# 3.net
KiCad netlist of a schematic drawn in Altium Designer
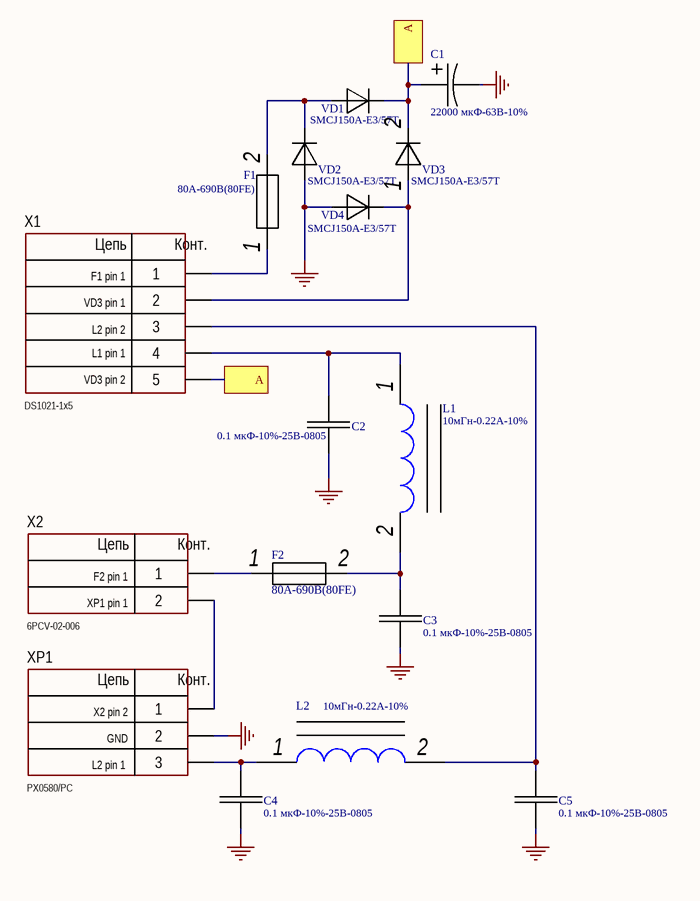
[diagram p0: Э3.SchDoc]

(export (version "E")
  (design (tool "Eeschema 10.0.6"))
  (components
    (comp (ref "C1")
      (value "22000 мкФ-63В-10%")
      (footprint "condpolar")
      (fields (field (name "MANUFACTURER") "Тайвань") (field (name "PARTNUMBER") "ECAP22000uF/63V,85°C"))
      (libsource (lib "resistor") (part "конденсатор_поляр"))
    )
    (comp (ref "C2")
      (value "0.1 мкФ-10%-25В-0805")
      (footprint "Condensator")
      (fields
        (field (name "MANUFACTURER") "Murata Electronics")
        (field (name "PARTNUMBER") "GRM21BR71E104KA01L")
      )
      (libsource (lib "resistor") (part "конденсатор"))
    )
    (comp (ref "C3")
      (value "0.1 мкФ-10%-25В-0805")
      (footprint "Condensator")
      (fields
        (field (name "MANUFACTURER") "Murata Electronics")
        (field (name "PARTNUMBER") "GRM21BR71E104KA01L")
      )
      (libsource (lib "resistor") (part "конденсатор"))
    )
    (comp (ref "C4")
      (value "0.1 мкФ-10%-25В-0805")
      (footprint "Condensator")
      (fields
        (field (name "MANUFACTURER") "Murata Electronics")
        (field (name "PARTNUMBER") "GRM21BR71E104KA01L")
      )
      (libsource (lib "resistor") (part "конденсатор"))
    )
    (comp (ref "C5")
      (value "0.1 мкФ-10%-25В-0805")
      (footprint "Condensator")
      (fields
        (field (name "MANUFACTURER") "Murata Electronics")
        (field (name "PARTNUMBER") "GRM21BR71E104KA01L")
      )
      (libsource (lib "resistor") (part "конденсатор"))
    )
    (comp (ref "F1")
      (value "80А-690В(80FE)")
      (footprint "FUSE 80")
      (fields (field (name "MANUFACTURER") "Eaton") (field (name "PARTNUMBER") "80FE"))
      (libsource (lib "resistor") (part "FUSE"))
    )
    (comp (ref "F2")
      (value "80А-690В(80FE)")
      (footprint "FUSE 80")
      (fields (field (name "MANUFACTURER") "Eaton") (field (name "PARTNUMBER") "80FE"))
      (libsource (lib "") (part "FUSE_1"))
    )
    (comp (ref "L1")
      (value "10мГн-0.22A-10%")
      (footprint "inductor")
      (fields (field (name "MANUFACTURER") "Kemet Electronics") (field (name "PARTNUMBER") "SBC6-103-161"))
      (libsource (lib "resistor") (part "inductor"))
    )
    (comp (ref "L2")
      (value "10мГн-0.22A-10%")
      (footprint "inductor")
      (fields (field (name "MANUFACTURER") "Kemet Electronics"))
      (libsource (lib "resistor") (part "inductor"))
    )
    (comp (ref "VD1")
      (value "SMCJ150A-E3/57T")
      (footprint "DIOD")
      (fields (field (name "MANUFACTURER") "VISHAY INTERTECHNOLOGY INC."))
      (libsource (lib "resistor") (part "Diod"))
    )
    (comp (ref "VD2")
      (value "SMCJ150A-E3/57T")
      (footprint "DIOD")
      (fields (field (name "MANUFACTURER") "VISHAY INTERTECHNOLOGY INC."))
      (libsource (lib "resistor") (part "Diod"))
    )
    (comp (ref "VD3")
      (value "SMCJ150A-E3/57T")
      (footprint "DIOD")
      (fields (field (name "MANUFACTURER") "VISHAY INTERTECHNOLOGY INC."))
      (libsource (lib "") (part "Diod_1"))
    )
    (comp (ref "VD4")
      (value "SMCJ150A-E3/57T")
      (footprint "DIOD")
      (fields (field (name "MANUFACTURER") "VISHAY INTERTECHNOLOGY INC."))
      (libsource (lib "resistor") (part "Diod"))
    )
    (comp (ref "X1")
      (value "~")
      (footprint "CON: PLS-5")
      (fields
        (field (name "MANUFACTURER") "Connfly")
        (field (name "VALUEMANUFACTURERPARTNUMBER") "Connector, 5pin, 2.54mm, 500VAC, 3A")
        (field (name "PARTNUMBER") "PLS-5")
        (field (name "COMMENTTEXT") "DS1021-1x5")
      )
      (libsource (lib "connector") (part "PLS-5"))
    )
    (comp (ref "X2")
      (value "~")
      (footprint "CON: 6PCV-02-006")
      (fields
        (field (name "MANUFACTURER") "TE Connectivity")
        (field (name "VALUEMANUFACTURERPARTNUMBER") "Connector, 2pin, 9.53mm, 300VAC, 25A")
        (field (name "PARTNUMBER") "6PCV-02-006")
        (field (name "COMMENTTEXT") "6PCV-02-006")
      )
      (libsource (lib "connector") (part "Connector_6PCV-02"))
    )
    (comp (ref "XP1")
      (value "~")
      (footprint "AC")
      (fields
        (field (name "MANUFACTURER") "Connfly")
        (field (name "VALUEMANUFACTURERPARTNUMBER") "Connector, 3pin, 2.54mm, 250VAC, 3A")
        (field (name "PARTNUMBER") "WF-3")
        (field (name "COMMENTTEXT") "PX0580/PC")
      )
      (libsource (lib "connector") (part "WF-3"))
    )
  )
  (nets
    (net (code "1") (name "/A") (class "Default")
      (node (ref "C1") (pin "2") (pinfunction "2_2") (pintype "passive"))
      (node (ref "VD1") (pin "2") (pinfunction "2_2") (pintype "passive"))
      (node (ref "VD3") (pin "2") (pinfunction "2_2") (pintype "passive"))
      (node (ref "X1") (pin "5") (pinfunction "5_5") (pintype "power_in"))
    )
    (net (code "2") (name "<NO NET>") (class "Default")
      (node (ref "C1") (pin "1") (pinfunction "1_1") (pintype "passive"))
      (node (ref "C2") (pin "1") (pinfunction "1_1") (pintype "passive"))
      (node (ref "C3") (pin "1") (pinfunction "1_1") (pintype "passive"))
      (node (ref "C4") (pin "2") (pinfunction "2_2") (pintype "passive"))
      (node (ref "C5") (pin "1") (pinfunction "1_1") (pintype "passive"))
      (node (ref "VD2") (pin "1") (pinfunction "1_1") (pintype "passive"))
      (node (ref "VD4") (pin "1") (pinfunction "1_1") (pintype "passive"))
      (node (ref "XP1") (pin "2") (pinfunction "2_2") (pintype "passive"))
    )
    (net (code "3") (name "Net-(C2-Pad2)") (class "Default")
      (node (ref "C2") (pin "2") (pinfunction "2_2") (pintype "passive"))
      (node (ref "L1") (pin "1") (pinfunction "1_1") (pintype "passive"))
      (node (ref "X1") (pin "4") (pinfunction "4_4") (pintype "power_in"))
    )
    (net (code "4") (name "Net-(C3-Pad2)") (class "Default")
      (node (ref "C3") (pin "2") (pinfunction "2_2") (pintype "passive"))
      (node (ref "F2") (pin "2") (pinfunction "2_2") (pintype "passive"))
      (node (ref "L1") (pin "2") (pinfunction "2_2") (pintype "passive"))
    )
    (net (code "5") (name "Net-(C4-Pad1)") (class "Default")
      (node (ref "C4") (pin "1") (pinfunction "1_1") (pintype "passive"))
      (node (ref "L2") (pin "1") (pinfunction "1_1") (pintype "passive"))
      (node (ref "XP1") (pin "3") (pinfunction "3_3") (pintype "power_in"))
    )
    (net (code "6") (name "Net-(C5-Pad2)") (class "Default")
      (node (ref "C5") (pin "2") (pinfunction "2_2") (pintype "passive"))
      (node (ref "L2") (pin "2") (pinfunction "2_2") (pintype "passive"))
      (node (ref "X1") (pin "3") (pinfunction "3_3") (pintype "power_in"))
    )
    (net (code "7") (name "Net-(F1-Pad1)") (class "Default")
      (node (ref "F1") (pin "1") (pinfunction "1_1") (pintype "passive"))
      (node (ref "X1") (pin "1") (pinfunction "1_1") (pintype "passive"))
    )
    (net (code "8") (name "Net-(F1-Pad2)") (class "Default")
      (node (ref "F1") (pin "2") (pinfunction "2_2") (pintype "passive"))
      (node (ref "VD1") (pin "1") (pinfunction "1_1") (pintype "passive"))
      (node (ref "VD2") (pin "2") (pinfunction "2_2") (pintype "passive"))
    )
    (net (code "9") (name "Net-(F2-Pad1)") (class "Default")
      (node (ref "F2") (pin "1") (pinfunction "1_1") (pintype "passive"))
      (node (ref "X2") (pin "1") (pinfunction "1_1") (pintype "passive"))
    )
    (net (code "10") (name "Net-(VD3-Pad1)") (class "Default")
      (node (ref "VD3") (pin "1") (pinfunction "1_1") (pintype "passive"))
      (node (ref "VD4") (pin "2") (pinfunction "2_2") (pintype "passive"))
      (node (ref "X1") (pin "2") (pinfunction "2_2") (pintype "passive"))
    )
    (net (code "11") (name "Net-(X2-Pad2)") (class "Default")
      (node (ref "X2") (pin "2") (pinfunction "2_2") (pintype "passive"))
      (node (ref "XP1") (pin "1") (pinfunction "1_1") (pintype "passive"))
    )
  )
)
